# BQ76952_AFE.net
KiCad netlist of a schematic drawn in Altium Designer
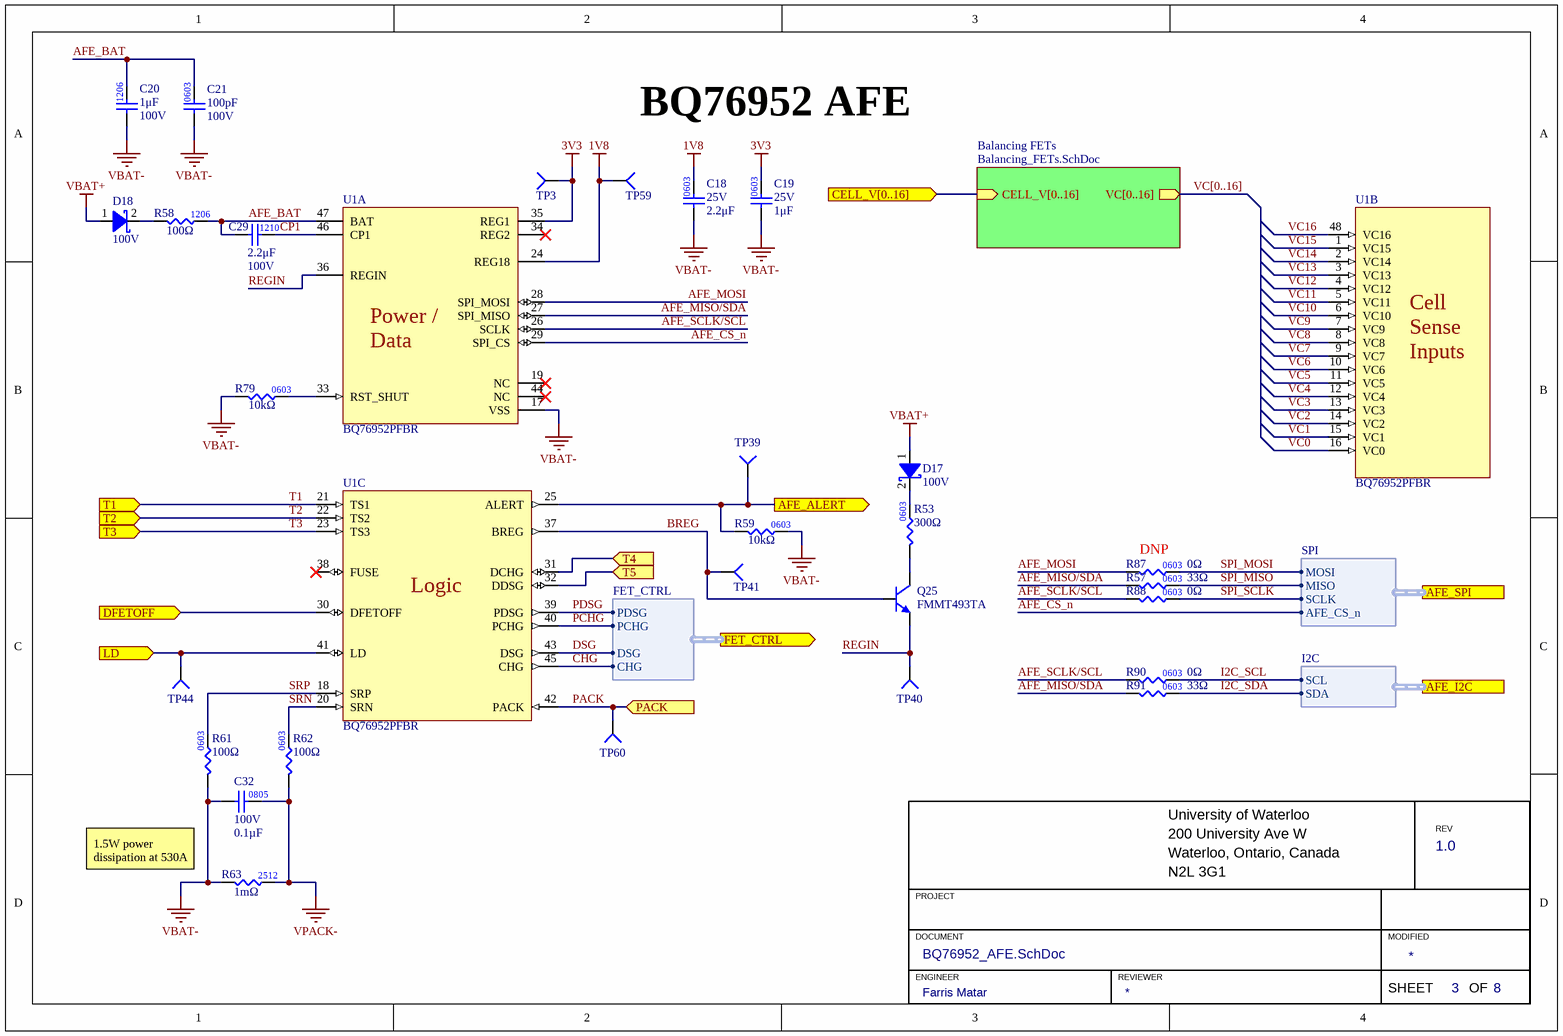
[diagram p0: BQ76952_AFE.SchDoc]

(export (version "E")
  (design (tool "Eeschema 10.0.6"))
  (components
    (comp (ref "C18")
      (value "2.2μF")
      (footprint "CAP0603")
      (description "CAP CER 2.2UF 25V X5R 0603")
      (fields (field (name "VOLTAGE RATING") "25V") (field (name "Comment") "CAP_2.2uF_25V_0603"))
      (libsource (lib "Personal_Schematic_Library_2022") (part "CAP_2.2uF_25V_0603"))
    )
    (comp (ref "C19")
      (value "1μF")
      (footprint "CAP0603")
      (description "CAP CER 1UF 25V X5R 0603")
      (fields (field (name "VOLTAGE RATING") "25V") (field (name "Comment") "CAP_1uF_25V_0603"))
      (libsource (lib "Personal_Schematic_Library_2022") (part "CAP_1uF_25V_0603"))
    )
    (comp (ref "C20")
      (value "1μF")
      (footprint "CAP1206")
      (description "CAP CER 1UF 100V X7R 1206")
      (fields (field (name "VOLTAGE RATING") "100V") (field (name "Comment") "CAP_1uF_100V_1206"))
      (libsource (lib "Personal_Schematic_Library_2022") (part "CAP_1uF_100V_1206"))
    )
    (comp (ref "C21")
      (value "100pF")
      (footprint "CAP2012")
      (description "CAP CER 100PF 100V X7R 0603")
      (fields (field (name "VOLTAGE RATING") "100V") (field (name "Comment") "CAP_100pF_100V_0603"))
      (libsource (lib "Personal_Schematic_Library_2022") (part "CAP_100pF_100V_0603"))
    )
    (comp (ref "C29")
      (value "2.2μF")
      (footprint "CAP1210")
      (description "CAP CER 2.2UF 100V X7R 1210")
      (fields (field (name "VOLTAGE RATING") "100V") (field (name "Comment") "CAP_2.2uF_100V_1210"))
      (libsource (lib "Personal_Schematic_Library_2022") (part "CAP_2.2uF_100V_1210"))
    )
    (comp (ref "C32")
      (value "0.1µF")
      (footprint "CAP0805")
      (description "CAP CER 0.1UF 100V X7R 0805")
      (fields (field (name "VOLTAGE RATING") "100V") (field (name "Comment") "CAP_0.1uF_100V_0805"))
      (libsource (lib "Personal_Schematic_Library_2022") (part "CAP_0.1uF_100V_0805"))
    )
    (comp (ref "D17")
      (value "DIO_SCHOTTKY_100V_1A")
      (footprint "SOD-123_FLAT")
      (description "DIODE SCHOTTKY 100V 1A SOD-123F")
      (fields (field (name "VR (MAX)") "100V"))
      (libsource (lib "Personal_Schematic_Library_2022") (part "DIO_SCHOTTKY_100V_1A"))
    )
    (comp (ref "D18")
      (value "DIO_SCHOTTKY_100V_1A")
      (footprint "SOD-123_FLAT")
      (description "DIODE SCHOTTKY 100V 1A SOD-123F")
      (fields (field (name "VR (MAX)") "100V"))
      (libsource (lib "Personal_Schematic_Library_2022") (part "DIO_SCHOTTKY_100V_1A"))
    )
    (comp (ref "Q25")
      (value "NPN_100V_1A")
      (footprint "SOT23-3")
      (description "TRANS NPN 100V 1A SOT23-3")
      (fields (field (name "MANUFACTURER PART NUMBER 1") "FMMT493TA"))
      (libsource (lib "Personal_Schematic_Library_2022") (part "NPN_100V_1A"))
    )
    (comp (ref "R53")
      (value "300Ω")
      (footprint "RES0603")
      (description "RES 200 OHM 1% 1/10W 0603")
      (fields (field (name "TOLERANCE") "1%") (field (name "Comment") "RES_300Ω_0603_1%"))
      (libsource (lib "Personal_Schematic_Library_2022") (part "RES_300Ω_0603_1%"))
    )
    (comp (ref "R57")
      (value "33Ω")
      (footprint "RES0603")
      (description "RES 33 OHM 1% 1/10W 0603")
      (fields (field (name "Comment") "RES_33Ω_0603_1%"))
      (libsource (lib "Personal_Schematic_Library_2022") (part "RES_33Ω_0603_1%"))
    )
    (comp (ref "R58")
      (value "100Ω")
      (footprint "RES1206")
      (description "RES 100 OHM 1% 1/4W 1206")
      (fields (field (name "Comment") "RES_100Ω_1206_1%"))
      (libsource (lib "Personal_Schematic_Library_2022") (part "RES_100Ω_1206_1%"))
    )
    (comp (ref "R59")
      (value "10kΩ")
      (footprint "RES0603")
      (description "RES 10K OHM 1% 1/8W 0603")
      (fields (field (name "Comment") "RES_10kΩ_0603_1%"))
      (libsource (lib "Personal_Schematic_Library_2022") (part "RES_10kΩ_0603_1%"))
    )
    (comp (ref "R61")
      (value "100Ω")
      (footprint "RES0603")
      (description "RES 100 OHM 1% 1/10W 0603")
      (fields (field (name "Comment") "RES_100Ω_0603_1%"))
      (libsource (lib "Personal_Schematic_Library_2022") (part "RES_100Ω_0603_1%"))
    )
    (comp (ref "R62")
      (value "100Ω")
      (footprint "RES0603")
      (description "RES 100 OHM 1% 1/10W 0603")
      (fields (field (name "Comment") "RES_100Ω_0603_1%"))
      (libsource (lib "Personal_Schematic_Library_2022") (part "RES_100Ω_0603_1%"))
    )
    (comp (ref "R63")
      (value "1mΩ")
      (footprint "RESC6532X75N")
      (description "RES 1 mOHM 1% 3W 2512")
      (fields (field (name "Comment") "RES_1mΩ_2512_1%"))
      (libsource (lib "Personal_Schematic_Library_2022") (part "RES_1mΩ_2512_1%"))
    )
    (comp (ref "R79")
      (value "10kΩ")
      (footprint "RES0603")
      (description "RES 10K OHM 1% 1/8W 0603")
      (fields (field (name "Comment") "RES_10kΩ_0603_1%"))
      (libsource (lib "Personal_Schematic_Library_2022") (part "RES_10kΩ_0603_1%"))
    )
    (comp (ref "R87")
      (value "0Ω")
      (footprint "RES0603")
      (description "RES 0 OHM JUMPER 1/10W 0603")
      (fields (field (name "Comment") "RES_0Ω_0603"))
      (libsource (lib "Personal_Schematic_Library_2022") (part "RES_0Ω_0603"))
    )
    (comp (ref "R88")
      (value "0Ω")
      (footprint "RES0603")
      (description "RES 0 OHM JUMPER 1/10W 0603")
      (fields (field (name "Comment") "RES_0Ω_0603"))
      (libsource (lib "Personal_Schematic_Library_2022") (part "RES_0Ω_0603"))
    )
    (comp (ref "R90")
      (value "0Ω")
      (footprint "RES0603")
      (description "RES 0 OHM JUMPER 1/10W 0603")
      (fields (field (name "Comment") "RES_0Ω_0603"))
      (libsource (lib "Personal_Schematic_Library_2022") (part "RES_0Ω_0603"))
    )
    (comp (ref "R91")
      (value "33Ω")
      (footprint "RES0603")
      (description "RES 33 OHM 1% 1/10W 0603")
      (fields (field (name "Comment") "RES_33Ω_0603_1%"))
      (libsource (lib "Personal_Schematic_Library_2022") (part "RES_33Ω_0603_1%"))
    )
    (comp (ref "TP3")
      (value "TESTPOINT_SMD_LOOP")
      (footprint "S1751-46R")
      (description "TESTPOINT SMD LOOP")
      (libsource (lib "UWRT_Schematic_Library_2020") (part "TESTPOINT_SMD_LOOP"))
    )
    (comp (ref "TP39")
      (value "TESTPOINT_1MM_CIRCLE")
      (footprint "TESTPOINT_CIRCLE_1MM")
      (description "TESTPOINT 1MM CIRCLE")
      (libsource (lib "Personal_Schematic_Library_2022") (part "TESTPOINT_1MM_CIRCLE"))
    )
    (comp (ref "TP40")
      (value "TESTPOINT_1MM_CIRCLE")
      (footprint "TESTPOINT_CIRCLE_1MM")
      (description "TESTPOINT 1MM CIRCLE")
      (libsource (lib "Personal_Schematic_Library_2022") (part "TESTPOINT_1MM_CIRCLE"))
    )
    (comp (ref "TP41")
      (value "TESTPOINT_1MM_CIRCLE")
      (footprint "TESTPOINT_CIRCLE_1MM")
      (description "TESTPOINT 1MM CIRCLE")
      (libsource (lib "Personal_Schematic_Library_2022") (part "TESTPOINT_1MM_CIRCLE"))
    )
    (comp (ref "TP44")
      (value "TESTPOINT_1MM_CIRCLE")
      (footprint "TESTPOINT_CIRCLE_1MM")
      (description "TESTPOINT 1MM CIRCLE")
      (libsource (lib "Personal_Schematic_Library_2022") (part "TESTPOINT_1MM_CIRCLE"))
    )
    (comp (ref "TP59")
      (value "TESTPOINT_1MM_SQUARE")
      (footprint "TESTPOINT_SQUARE_1MM")
      (description "TESTPOINT 1MM SQUARE")
      (libsource (lib "Personal_Schematic_Library_2022") (part "TESTPOINT_1MM_SQUARE"))
    )
    (comp (ref "TP60")
      (value "TESTPOINT_1MM_CIRCLE")
      (footprint "TESTPOINT_CIRCLE_1MM")
      (description "TESTPOINT 1MM CIRCLE")
      (libsource (lib "Personal_Schematic_Library_2022") (part "TESTPOINT_1MM_CIRCLE"))
    )
    (comp (ref "U1")
      (value "BQ76952PFBR")
      (footprint "TI_48-TQFP")
      (description "IC BAT LIFEPO4/LI-ION 3-16C TQFP")
      (libsource (lib "Personal_Schematic_Library_2022") (part "BQ7695204PFBR"))
    )
  )
  (nets
    (net (code "21") (name "/AFE_ALERT") (class "Default")
      (node (ref "R59") (pin "1") (pinfunction "1_1") (pintype "passive"))
      (node (ref "TP39") (pin "1") (pinfunction "=value_1") (pintype "passive"))
      (node (ref "U1") (pin "25") (pinfunction "ALERT_25") (pintype "output"))
    )
    (net (code "22") (name "/AFE_BAT") (class "Default")
      (node (ref "C20") (pin "2") (pinfunction "2_2") (pintype "passive"))
      (node (ref "C21") (pin "2") (pinfunction "2_2") (pintype "passive"))
      (node (ref "C29") (pin "1") (pinfunction "1_1") (pintype "passive"))
      (node (ref "R58") (pin "2") (pinfunction "2_2") (pintype "passive"))
      (node (ref "U1") (pin "47") (pinfunction "BAT_47") (pintype "power_in"))
    )
    (net (code "23") (name "/AFE_CS_n") (class "Default")
      (node (ref "U1") (pin "29") (pinfunction "SPI_CS_29") (pintype "bidirectional"))
    )
    (net (code "24") (name "/AFE_MISO{slash}SDA") (class "Default")
      (node (ref "R57") (pin "1") (pinfunction "1_1") (pintype "passive"))
      (node (ref "R91") (pin "1") (pinfunction "1_1") (pintype "passive"))
      (node (ref "U1") (pin "27") (pinfunction "SPI_MISO_27") (pintype "bidirectional"))
    )
    (net (code "25") (name "/AFE_MOSI") (class "Default")
      (node (ref "R87") (pin "1") (pinfunction "1_1") (pintype "passive"))
      (node (ref "U1") (pin "28") (pinfunction "SPI_MOSI_28") (pintype "bidirectional"))
    )
    (net (code "26") (name "/AFE_SCLK{slash}SCL") (class "Default")
      (node (ref "R88") (pin "1") (pinfunction "1_1") (pintype "passive"))
      (node (ref "R90") (pin "1") (pinfunction "1_1") (pintype "passive"))
      (node (ref "U1") (pin "26") (pinfunction "SCLK_26") (pintype "bidirectional"))
    )
    (net (code "27") (name "/BREG") (class "Default")
      (node (ref "Q25") (pin "1") (pinfunction "B_1") (pintype "passive"))
      (node (ref "TP41") (pin "1") (pinfunction "=value_1") (pintype "passive"))
      (node (ref "U1") (pin "37") (pinfunction "BREG_37") (pintype "output"))
    )
    (net (code "29") (name "/CHG") (class "Default")
      (node (ref "U1") (pin "45") (pinfunction "CHG_45") (pintype "output"))
    )
    (net (code "30") (name "/CP1") (class "Default")
      (node (ref "C29") (pin "2") (pinfunction "2_2") (pintype "passive"))
      (node (ref "U1") (pin "46") (pinfunction "CP1_46") (pintype "power_in"))
    )
    (net (code "31") (name "/DFETOFF") (class "Default")
      (node (ref "U1") (pin "30") (pinfunction "DFETOFF_30") (pintype "bidirectional"))
    )
    (net (code "32") (name "/DSG") (class "Default")
      (node (ref "U1") (pin "43") (pinfunction "DSG_43") (pintype "output"))
    )
    (net (code "33") (name "/I2C_SCL") (class "Default")
      (node (ref "R90") (pin "2") (pinfunction "2_2") (pintype "passive"))
    )
    (net (code "34") (name "/I2C_SDA") (class "Default")
      (node (ref "R91") (pin "2") (pinfunction "2_2") (pintype "passive"))
    )
    (net (code "35") (name "/LD") (class "Default")
      (node (ref "TP44") (pin "1") (pinfunction "=value_1") (pintype "passive"))
      (node (ref "U1") (pin "41") (pinfunction "LD_41") (pintype "bidirectional"))
    )
    (net (code "36") (name "/PACK") (class "Default")
      (node (ref "TP60") (pin "1") (pinfunction "=value_1") (pintype "passive"))
      (node (ref "U1") (pin "42") (pinfunction "PACK_42") (pintype "input"))
    )
    (net (code "37") (name "/PCHG") (class "Default")
      (node (ref "U1") (pin "40") (pinfunction "PCHG_40") (pintype "output"))
    )
    (net (code "38") (name "/PDSG") (class "Default")
      (node (ref "U1") (pin "39") (pinfunction "PDSG_39") (pintype "output"))
    )
    (net (code "39") (name "/REGIN") (class "Default")
      (node (ref "Q25") (pin "2") (pinfunction "E_2") (pintype "passive"))
      (node (ref "TP40") (pin "1") (pinfunction "=value_1") (pintype "passive"))
      (node (ref "U1") (pin "36") (pinfunction "REGIN_36") (pintype "power_in"))
    )
    (net (code "40") (name "/SPI_MISO") (class "Default")
      (node (ref "R57") (pin "2") (pinfunction "2_2") (pintype "passive"))
    )
    (net (code "41") (name "/SPI_MOSI") (class "Default")
      (node (ref "R87") (pin "2") (pinfunction "2_2") (pintype "passive"))
    )
    (net (code "42") (name "/SPI_SCLK") (class "Default")
      (node (ref "R88") (pin "2") (pinfunction "2_2") (pintype "passive"))
    )
    (net (code "43") (name "/SRN") (class "Default")
      (node (ref "R62") (pin "2") (pinfunction "2_2") (pintype "passive"))
      (node (ref "U1") (pin "20") (pinfunction "SRN_20") (pintype "input"))
    )
    (net (code "44") (name "/SRP") (class "Default")
      (node (ref "R61") (pin "2") (pinfunction "2_2") (pintype "passive"))
      (node (ref "U1") (pin "18") (pinfunction "SRP_18") (pintype "input"))
    )
    (net (code "45") (name "/T1") (class "Default")
      (node (ref "U1") (pin "21") (pinfunction "TS1_21") (pintype "input"))
    )
    (net (code "46") (name "/T2") (class "Default")
      (node (ref "U1") (pin "22") (pinfunction "TS2_22") (pintype "input"))
    )
    (net (code "47") (name "/T3") (class "Default")
      (node (ref "U1") (pin "23") (pinfunction "TS3_23") (pintype "input"))
    )
    (net (code "48") (name "/T4") (class "Default")
      (node (ref "U1") (pin "31") (pinfunction "DCHG_31") (pintype "bidirectional"))
    )
    (net (code "49") (name "/T5") (class "Default")
      (node (ref "U1") (pin "32") (pinfunction "DDSG_32") (pintype "bidirectional"))
    )
    (net (code "50") (name "/VC0") (class "Default")
      (node (ref "U1") (pin "16") (pinfunction "VC0_16") (pintype "input"))
    )
    (net (code "51") (name "/VC1") (class "Default")
      (node (ref "U1") (pin "15") (pinfunction "VC1_15") (pintype "input"))
    )
    (net (code "52") (name "/VC2") (class "Default")
      (node (ref "U1") (pin "14") (pinfunction "VC2_14") (pintype "input"))
    )
    (net (code "53") (name "/VC3") (class "Default")
      (node (ref "U1") (pin "13") (pinfunction "VC3_13") (pintype "input"))
    )
    (net (code "54") (name "/VC4") (class "Default")
      (node (ref "U1") (pin "12") (pinfunction "VC4_12") (pintype "input"))
    )
    (net (code "55") (name "/VC5") (class "Default")
      (node (ref "U1") (pin "11") (pinfunction "VC5_11") (pintype "input"))
    )
    (net (code "56") (name "/VC6") (class "Default")
      (node (ref "U1") (pin "10") (pinfunction "VC6_10") (pintype "input"))
    )
    (net (code "57") (name "/VC7") (class "Default")
      (node (ref "U1") (pin "9") (pinfunction "VC7_9") (pintype "input"))
    )
    (net (code "58") (name "/VC8") (class "Default")
      (node (ref "U1") (pin "8") (pinfunction "VC8_8") (pintype "input"))
    )
    (net (code "59") (name "/VC9") (class "Default")
      (node (ref "U1") (pin "7") (pinfunction "VC9_7") (pintype "input"))
    )
    (net (code "60") (name "/VC10") (class "Default")
      (node (ref "U1") (pin "6") (pinfunction "VC10_6") (pintype "input"))
    )
    (net (code "61") (name "/VC11") (class "Default")
      (node (ref "U1") (pin "5") (pinfunction "VC11_5") (pintype "input"))
    )
    (net (code "62") (name "/VC12") (class "Default")
      (node (ref "U1") (pin "4") (pinfunction "VC12_4") (pintype "input"))
    )
    (net (code "63") (name "/VC13") (class "Default")
      (node (ref "U1") (pin "3") (pinfunction "VC13_3") (pintype "input"))
    )
    (net (code "64") (name "/VC14") (class "Default")
      (node (ref "U1") (pin "2") (pinfunction "VC14_2") (pintype "input"))
    )
    (net (code "65") (name "/VC15") (class "Default")
      (node (ref "U1") (pin "1") (pinfunction "VC15_1") (pintype "input"))
    )
    (net (code "66") (name "/VC16") (class "Default")
      (node (ref "U1") (pin "48") (pinfunction "VC16_48") (pintype "input"))
    )
    (net (code "71") (name "1V8") (class "Default")
      (node (ref "C18") (pin "2") (pinfunction "2_2") (pintype "passive"))
      (node (ref "TP59") (pin "1") (pinfunction "=value_1") (pintype "passive"))
      (node (ref "U1") (pin "24") (pinfunction "REG18_24") (pintype "power_in"))
    )
    (net (code "72") (name "3V3") (class "Default")
      (node (ref "C19") (pin "2") (pinfunction "2_2") (pintype "passive"))
      (node (ref "TP3") (pin "1") (pinfunction "=value_1") (pintype "passive"))
      (node (ref "U1") (pin "35") (pinfunction "REG1_35") (pintype "power_in"))
    )
    (net (code "73") (name "Net-(D17-Cathode)") (class "Default")
      (node (ref "D17") (pin "2") (pinfunction "Cathode_2") (pintype "passive"))
      (node (ref "R53") (pin "2") (pinfunction "2_2") (pintype "passive"))
    )
    (net (code "74") (name "Net-(D18-Cathode)") (class "Default")
      (node (ref "D18") (pin "2") (pinfunction "Cathode_2") (pintype "passive"))
      (node (ref "R58") (pin "1") (pinfunction "1_1") (pintype "passive"))
    )
    (net (code "75") (name "Net-(Q25-C)") (class "Default")
      (node (ref "Q25") (pin "3") (pinfunction "C_3") (pintype "passive"))
      (node (ref "R53") (pin "1") (pinfunction "1_1") (pintype "passive"))
    )
    (net (code "76") (name "Net-(U1A-RST_SHUT)") (class "Default")
      (node (ref "R79") (pin "2") (pinfunction "2_2") (pintype "passive"))
      (node (ref "U1") (pin "33") (pinfunction "RST_SHUT_33") (pintype "input"))
    )
    (net (code "77") (name "VBAT+") (class "Default")
      (node (ref "D17") (pin "1") (pinfunction "Anode_1") (pintype "passive"))
      (node (ref "D18") (pin "1") (pinfunction "Anode_1") (pintype "passive"))
    )
    (net (code "78") (name "VBAT-") (class "Default")
      (node (ref "C18") (pin "1") (pinfunction "1_1") (pintype "passive"))
      (node (ref "C19") (pin "1") (pinfunction "1_1") (pintype "passive"))
      (node (ref "C20") (pin "1") (pinfunction "1_1") (pintype "passive"))
      (node (ref "C21") (pin "1") (pinfunction "1_1") (pintype "passive"))
      (node (ref "C32") (pin "1") (pinfunction "1_1") (pintype "passive"))
      (node (ref "R59") (pin "2") (pinfunction "2_2") (pintype "passive"))
      (node (ref "R61") (pin "1") (pinfunction "1_1") (pintype "passive"))
      (node (ref "R63") (pin "1") (pinfunction "1_1") (pintype "passive"))
      (node (ref "R79") (pin "1") (pinfunction "1_1") (pintype "passive"))
      (node (ref "U1") (pin "17") (pinfunction "VSS_17") (pintype "power_in"))
    )
    (net (code "79") (name "VPACK-") (class "Default")
      (node (ref "C32") (pin "2") (pinfunction "2_2") (pintype "passive"))
      (node (ref "R62") (pin "1") (pinfunction "1_1") (pintype "passive"))
      (node (ref "R63") (pin "2") (pinfunction "2_2") (pintype "passive"))
    )
    (net (code "80") (name "unconnected-(U1A-NC-Pad19)") (class "Default")
      (node (ref "U1") (pin "19") (pinfunction "NC_19") (pintype "passive+no_connect"))
    )
    (net (code "81") (name "unconnected-(U1A-NC-Pad44)") (class "Default")
      (node (ref "U1") (pin "44") (pinfunction "NC_44") (pintype "passive+no_connect"))
    )
    (net (code "82") (name "unconnected-(U1A-REG2-Pad34)") (class "Default")
      (node (ref "U1") (pin "34") (pinfunction "REG2_34") (pintype "power_in+no_connect"))
    )
    (net (code "83") (name "unconnected-(U1C-FUSE-Pad38)") (class "Default")
      (node (ref "U1") (pin "38") (pinfunction "FUSE_38") (pintype "bidirectional+no_connect"))
    )
  )
)
